# Sheet1.net
KiCad netlist of a schematic drawn in Altium Designer
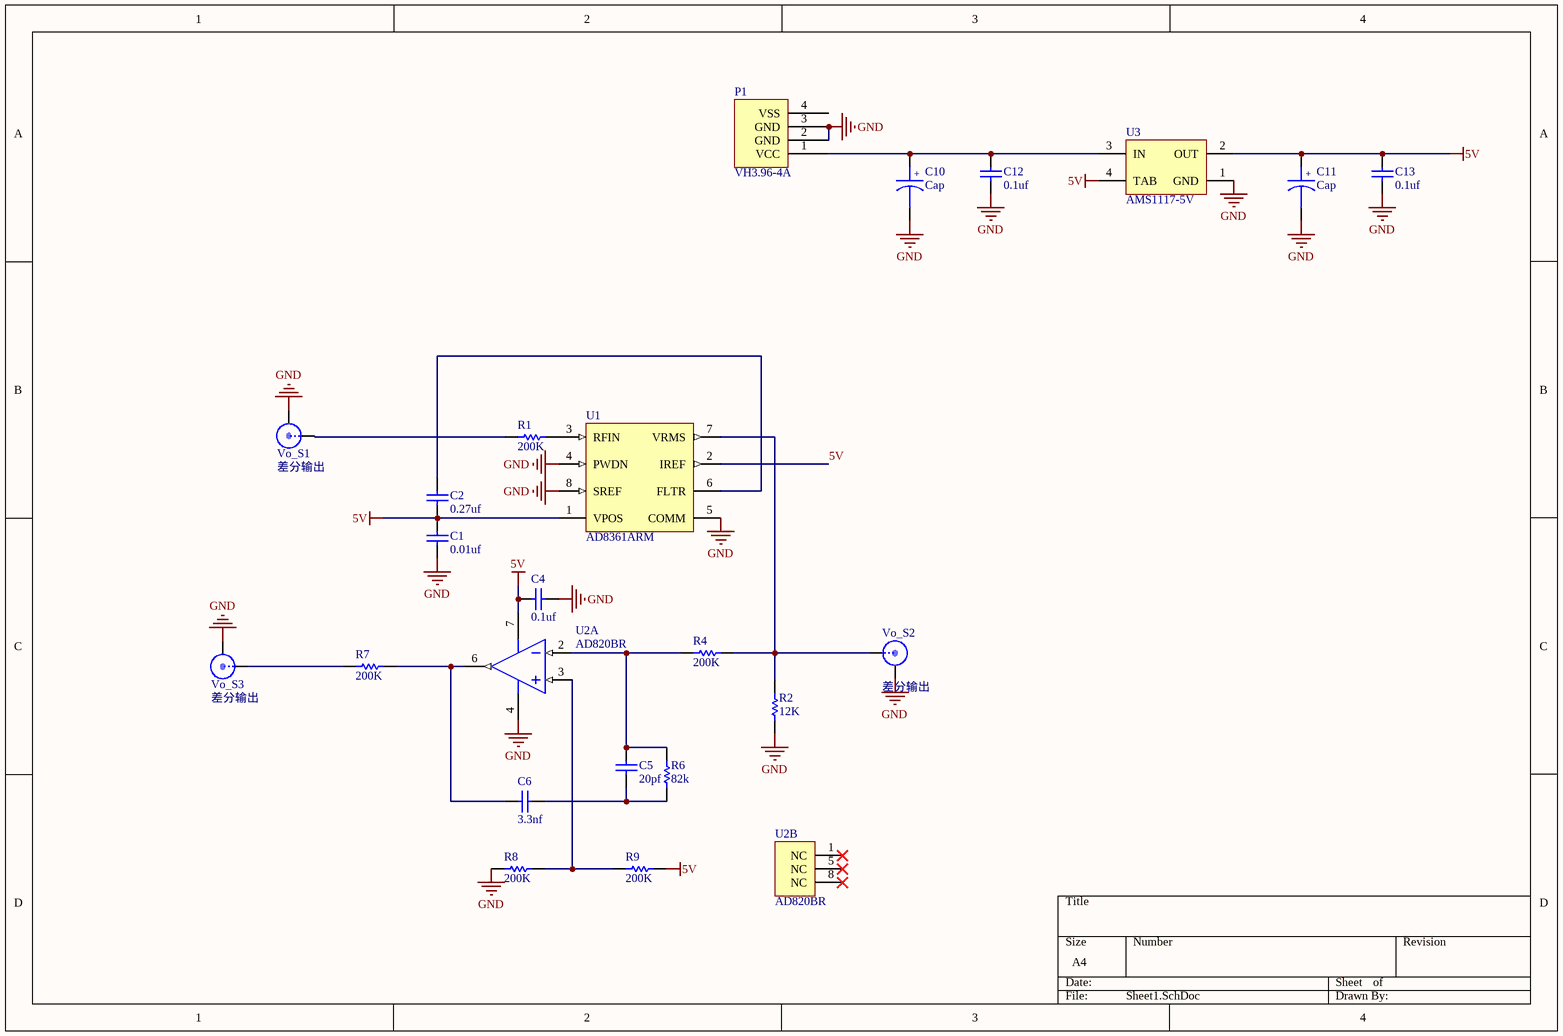
[diagram p0: Sheet1.SchDoc]

(export (version "E")
  (design (tool "Eeschema 10.0.6"))
  (components
    (comp (ref "C1") (value "0.01uf") (footprint "0603C") (libsource (lib "Schlib1") (part "Cap")))
    (comp (ref "C2") (value "0.27uf") (footprint "0603C") (libsource (lib "Schlib1") (part "Cap")))
    (comp (ref "C4") (value "0.1uf") (footprint "0603C") (libsource (lib "Schlib1") (part "Cap")))
    (comp (ref "C5") (value "20pf") (footprint "0603C") (libsource (lib "Schlib1") (part "Cap")))
    (comp (ref "C6") (value "3.3nf") (footprint "0603C") (libsource (lib "Schlib1") (part "Cap")))
    (comp (ref "C10")
      (value "Cap")
      (footprint "3216C-TYPE_A")
      (libsource (lib "Schlib1") (part "Tantalium Cap"))
    )
    (comp (ref "C11")
      (value "Cap")
      (footprint "3216C-TYPE_A")
      (libsource (lib "Schlib1") (part "Tantalium Cap"))
    )
    (comp (ref "C12") (value "0.1uf") (footprint "0805") (libsource (lib "Schlib1") (part "Cap")))
    (comp (ref "C13") (value "0.1uf") (footprint "0805") (libsource (lib "Schlib1") (part "Cap")))
    (comp (ref "P1")
      (value "VH3.96-4A")
      (footprint "VH3.96-4P")
      (libsource (lib "Schlib1") (part "VH3.96-4A"))
    )
    (comp (ref "R1") (value "200K") (footprint "0603R") (libsource (lib "Schlib1") (part "Res")))
    (comp (ref "R2") (value "12K") (footprint "0603R") (libsource (lib "Schlib1") (part "Res")))
    (comp (ref "R4") (value "200K") (footprint "0603R") (libsource (lib "Schlib1") (part "Res")))
    (comp (ref "R6") (value "82k") (footprint "0603R") (libsource (lib "Schlib1") (part "Res")))
    (comp (ref "R7") (value "200K") (footprint "0603R") (libsource (lib "Schlib1") (part "Res")))
    (comp (ref "R8") (value "200K") (footprint "0603R") (libsource (lib "Schlib1") (part "Res")))
    (comp (ref "R9") (value "200K") (footprint "0603R") (libsource (lib "Schlib1") (part "Res")))
    (comp (ref "U1")
      (value "AD8361ARM")
      (footprint "ADI-RM-8_N")
      (description "LF to 2.5 GHz TruPwr?Detector, 5祍 Response Time, RM-8, 50 Tube")
      (libsource (lib "Schlib1") (part "AD8361ARM"))
    )
    (comp (ref "U2")
      (value "AD820BR")
      (footprint "ADI-R-8_N")
      (fields (field (name "GENERIC PART NUMBER") "AD820") (field (name "MANUFACTURER") "Analog Devices"))
      (libsource (lib "Schlib1") (part "AD820BR"))
    )
    (comp (ref "U3")
      (value "AMS1117-5V")
      (footprint "SOT-223")
      (libsource (lib "Schlib1") (part "AMS1117-3.3V"))
    )
    (comp (ref "Vo_S1") (value "差分输出") (footprint "SMA-LYING") (libsource (lib "Schlib1") (part "SMA")))
    (comp (ref "Vo_S2") (value "差分输出") (footprint "SMA-LYING") (libsource (lib "Schlib1") (part "SMA")))
    (comp (ref "Vo_S3") (value "差分输出") (footprint "SMA-LYING") (libsource (lib "Schlib1") (part "SMA")))
  )
  (nets
    (net (code "1") (name "5V") (class "Default")
      (node (ref "C1") (pin "2") (pinfunction "2_2") (pintype "passive"))
      (node (ref "C11") (pin "1") (pinfunction "1_1") (pintype "passive"))
      (node (ref "C13") (pin "2") (pinfunction "2_2") (pintype "passive"))
      (node (ref "C2") (pin "1") (pinfunction "1_1") (pintype "passive"))
      (node (ref "C4") (pin "1") (pinfunction "1_1") (pintype "passive"))
      (node (ref "R9") (pin "2") (pinfunction "2_2") (pintype "passive"))
      (node (ref "U1") (pin "1") (pinfunction "VPOS_1") (pintype "power_in"))
      (node (ref "U1") (pin "2") (pinfunction "IREF_2") (pintype "output"))
      (node (ref "U2") (pin "7") (pinfunction "+VS_7") (pintype "power_in"))
      (node (ref "U3") (pin "2") (pinfunction "OUT_2") (pintype "power_in"))
      (node (ref "U3") (pin "4") (pinfunction "TAB_4") (pintype "power_in"))
    )
    (net (code "2") (name "GND") (class "Default")
      (node (ref "C1") (pin "1") (pinfunction "1_1") (pintype "passive"))
      (node (ref "C10") (pin "2") (pinfunction "2_2") (pintype "passive"))
      (node (ref "C11") (pin "2") (pinfunction "2_2") (pintype "passive"))
      (node (ref "C12") (pin "1") (pinfunction "1_1") (pintype "passive"))
      (node (ref "C13") (pin "1") (pinfunction "1_1") (pintype "passive"))
      (node (ref "C4") (pin "2") (pinfunction "2_2") (pintype "passive"))
      (node (ref "P1") (pin "2") (pinfunction "GND_2") (pintype "passive"))
      (node (ref "P1") (pin "3") (pinfunction "GND_3") (pintype "passive"))
      (node (ref "R2") (pin "1") (pinfunction "1_1") (pintype "passive"))
      (node (ref "R8") (pin "1") (pinfunction "1_1") (pintype "passive"))
      (node (ref "U1") (pin "4") (pinfunction "PWDN_4") (pintype "input"))
      (node (ref "U1") (pin "5") (pinfunction "COMM_5") (pintype "power_in"))
      (node (ref "U1") (pin "8") (pinfunction "SREF_8") (pintype "input"))
      (node (ref "U2") (pin "4") (pinfunction "-VS_4") (pintype "power_in"))
      (node (ref "U3") (pin "1") (pinfunction "GND_1") (pintype "power_in"))
      (node (ref "Vo_S1") (pin "1") (pinfunction "1_1") (pintype "passive"))
      (node (ref "Vo_S2") (pin "1") (pinfunction "1_1") (pintype "passive"))
      (node (ref "Vo_S3") (pin "1") (pinfunction "1_1") (pintype "passive"))
    )
    (net (code "3") (name "Net-(C5-Pad1)") (class "Default")
      (node (ref "C5") (pin "1") (pinfunction "1_1") (pintype "passive"))
      (node (ref "C6") (pin "1") (pinfunction "1_1") (pintype "passive"))
      (node (ref "R6") (pin "1") (pinfunction "1_1") (pintype "passive"))
    )
    (net (code "4") (name "Net-(P1-VCC)") (class "Default")
      (node (ref "C10") (pin "1") (pinfunction "1_1") (pintype "passive"))
      (node (ref "C12") (pin "2") (pinfunction "2_2") (pintype "passive"))
      (node (ref "P1") (pin "1") (pinfunction "VCC_1") (pintype "passive"))
      (node (ref "U3") (pin "3") (pinfunction "IN_3") (pintype "power_in"))
    )
    (net (code "5") (name "Net-(R1-Pad1)") (class "Default")
      (node (ref "R1") (pin "1") (pinfunction "1_1") (pintype "passive"))
      (node (ref "Vo_S1") (pin "0") (pinfunction "0_0") (pintype "passive"))
    )
    (net (code "6") (name "Net-(R7-Pad2)") (class "Default")
      (node (ref "R7") (pin "2") (pinfunction "2_2") (pintype "passive"))
      (node (ref "Vo_S3") (pin "0") (pinfunction "0_0") (pintype "passive"))
    )
    (net (code "7") (name "Net-(U1-FLTR)") (class "Default")
      (node (ref "C2") (pin "2") (pinfunction "2_2") (pintype "passive"))
      (node (ref "U1") (pin "6") (pinfunction "FLTR_6") (pintype "passive"))
    )
    (net (code "8") (name "Net-(U1-RFIN)") (class "Default")
      (node (ref "R1") (pin "2") (pinfunction "2_2") (pintype "passive"))
      (node (ref "U1") (pin "3") (pinfunction "RFIN_3") (pintype "input"))
    )
    (net (code "9") (name "Net-(U1-VRMS)") (class "Default")
      (node (ref "R2") (pin "2") (pinfunction "2_2") (pintype "passive"))
      (node (ref "R4") (pin "2") (pinfunction "2_2") (pintype "passive"))
      (node (ref "U1") (pin "7") (pinfunction "VRMS_7") (pintype "output"))
      (node (ref "Vo_S2") (pin "0") (pinfunction "0_0") (pintype "passive"))
    )
    (net (code "10") (name "Net-(U2A-+IN)") (class "Default")
      (node (ref "R8") (pin "2") (pinfunction "2_2") (pintype "passive"))
      (node (ref "R9") (pin "1") (pinfunction "1_1") (pintype "passive"))
      (node (ref "U2") (pin "3") (pinfunction "+IN_3") (pintype "input"))
    )
    (net (code "11") (name "Net-(U2A--IN)") (class "Default")
      (node (ref "C5") (pin "2") (pinfunction "2_2") (pintype "passive"))
      (node (ref "R4") (pin "1") (pinfunction "1_1") (pintype "passive"))
      (node (ref "R6") (pin "2") (pinfunction "2_2") (pintype "passive"))
      (node (ref "U2") (pin "2") (pinfunction "-IN_2") (pintype "input"))
    )
    (net (code "12") (name "Net-(U2A-VOUT)") (class "Default")
      (node (ref "C6") (pin "2") (pinfunction "2_2") (pintype "passive"))
      (node (ref "R7") (pin "1") (pinfunction "1_1") (pintype "passive"))
      (node (ref "U2") (pin "6") (pinfunction "VOUT_6") (pintype "output"))
    )
    (net (code "13") (name "unconnected-(P1-VSS-Pad4)") (class "Default")
      (node (ref "P1") (pin "4") (pinfunction "VSS_4") (pintype "passive"))
    )
    (net (code "14") (name "unconnected-(U2B-NC-Pad1)") (class "Default")
      (node (ref "U2") (pin "1") (pinfunction "NC_1") (pintype "passive+no_connect"))
    )
    (net (code "15") (name "unconnected-(U2B-NC-Pad5)") (class "Default")
      (node (ref "U2") (pin "5") (pinfunction "NC_5") (pintype "passive+no_connect"))
    )
    (net (code "16") (name "unconnected-(U2B-NC-Pad8)") (class "Default")
      (node (ref "U2") (pin "8") (pinfunction "NC_8") (pintype "passive+no_connect"))
    )
  )
)
